# schematic_BAR.net
KiCad netlist of a schematic drawn in EAGLE
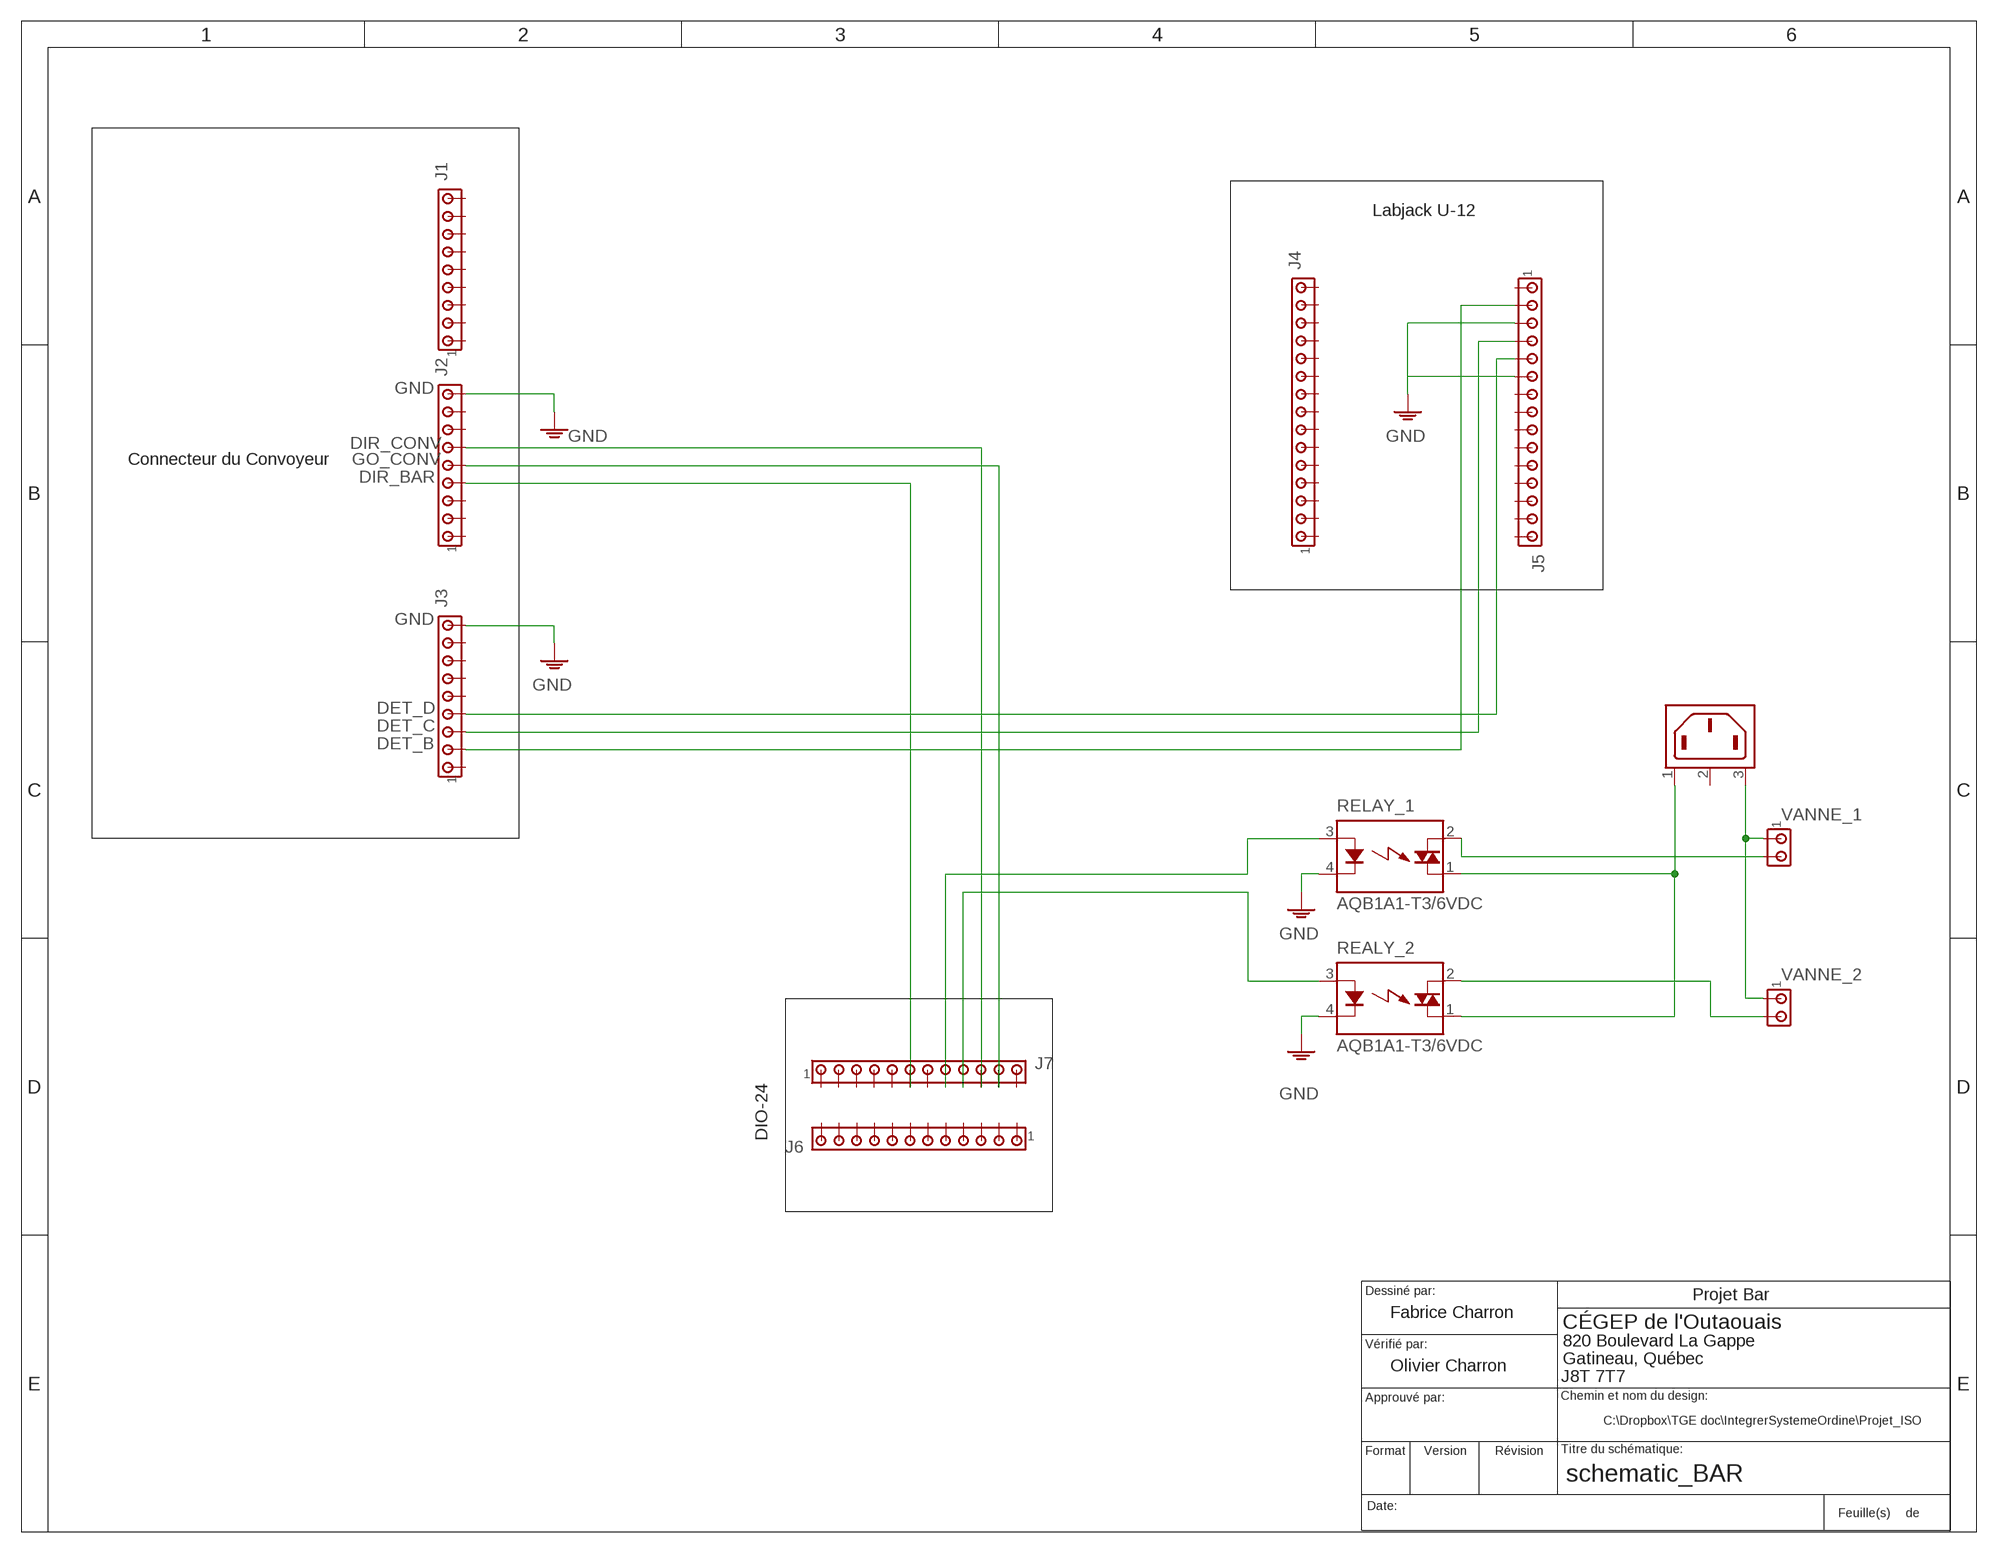
[diagram p0: schematic, sheet 1]

(export (version "E")
  (design (tool "Eeschema 10.0.6"))
  (components
    (comp (ref "J1")
      (value "MTA09-100")
      (footprint "eagle-import:10X09MTA")
      (libsource (lib "eagle-import") (part "MTA09-100"))
    )
    (comp (ref "J2")
      (value "MTA09-100")
      (footprint "eagle-import:10X09MTA")
      (libsource (lib "eagle-import") (part "MTA09-100"))
    )
    (comp (ref "J3")
      (value "MTA09-100")
      (footprint "eagle-import:10X09MTA")
      (libsource (lib "eagle-import") (part "MTA09-100"))
    )
    (comp (ref "J4")
      (value "MTA15-156")
      (footprint "eagle-import:1X15MTA")
      (libsource (lib "eagle-import") (part "MTA15-156"))
    )
    (comp (ref "J5")
      (value "MTA15-156")
      (footprint "eagle-import:1X15MTA")
      (libsource (lib "eagle-import") (part "MTA15-156"))
    )
    (comp (ref "J6")
      (value "MTA12-156")
      (footprint "eagle-import:1X12MTA")
      (libsource (lib "eagle-import") (part "MTA12-156"))
    )
    (comp (ref "J7")
      (value "MTA12-156")
      (footprint "eagle-import:1X12MTA")
      (libsource (lib "eagle-import") (part "MTA12-156"))
    )
    (comp (ref "REALY_2")
      (value "AQB1A1-T3/6VDC")
      (footprint "eagle-import:AQ-B")
      (libsource (lib "eagle-import") (part "AQB1A1-T3/6VDC"))
    )
    (comp (ref "RELAY_1")
      (value "AQB1A1-T3/6VDC")
      (footprint "eagle-import:AQ-B")
      (libsource (lib "eagle-import") (part "AQB1A1-T3/6VDC"))
    )
    (comp (ref "SOURCE_120V")
      (value "6ESRM-P")
      (footprint "eagle-import:6ESRM-P")
      (fields (field (name "MF") "TYCO ELECTRONICS"))
      (libsource (lib "eagle-import") (part "6ESRM-P"))
    )
    (comp (ref "VANNE_1")
      (value "MTA02-100")
      (footprint "eagle-import:10X02MTA")
      (libsource (lib "eagle-import") (part "MTA02-100"))
    )
    (comp (ref "VANNE_2")
      (value "MTA02-100")
      (footprint "eagle-import:10X02MTA")
      (libsource (lib "eagle-import") (part "MTA02-100"))
    )
  )
  (nets
    (net (code "1") (name "/DET_B") (class "Default")
      (node (ref "J3") (pin "2") (pinfunction "2_2") (pintype "passive"))
      (node (ref "J5") (pin "2") (pinfunction "2_2") (pintype "passive"))
    )
    (net (code "2") (name "/DET_C") (class "Default")
      (node (ref "J3") (pin "3") (pinfunction "3_3") (pintype "passive"))
      (node (ref "J5") (pin "4") (pinfunction "4_4") (pintype "passive"))
    )
    (net (code "3") (name "/DET_D") (class "Default")
      (node (ref "J3") (pin "4") (pinfunction "4_4") (pintype "passive"))
      (node (ref "J5") (pin "5") (pinfunction "5_5") (pintype "passive"))
    )
    (net (code "4") (name "/DIR_BAR") (class "Default")
      (node (ref "J2") (pin "4") (pinfunction "4_4") (pintype "passive"))
      (node (ref "J7") (pin "6") (pinfunction "6_6") (pintype "passive"))
    )
    (net (code "5") (name "/DIR_CONV") (class "Default")
      (node (ref "J2") (pin "6") (pinfunction "6_6") (pintype "passive"))
      (node (ref "J7") (pin "10") (pinfunction "10_10") (pintype "passive"))
    )
    (net (code "6") (name "/GO_CONV") (class "Default")
      (node (ref "J2") (pin "5") (pinfunction "5_5") (pintype "passive"))
      (node (ref "J7") (pin "11") (pinfunction "11_11") (pintype "passive"))
    )
    (net (code "7") (name "GND") (class "Default")
      (node (ref "J2") (pin "9") (pinfunction "9_9") (pintype "passive"))
      (node (ref "J3") (pin "9") (pinfunction "9_9") (pintype "passive"))
      (node (ref "J5") (pin "3") (pinfunction "3_3") (pintype "passive"))
      (node (ref "J5") (pin "6") (pinfunction "6_6") (pintype "passive"))
      (node (ref "REALY_2") (pin "4") (pinfunction "K_4") (pintype "passive"))
      (node (ref "RELAY_1") (pin "4") (pinfunction "K_4") (pintype "passive"))
    )
    (net (code "8") (name "Net-(REALY_2-A)") (class "Default")
      (node (ref "J7") (pin "9") (pinfunction "9_9") (pintype "passive"))
      (node (ref "REALY_2") (pin "3") (pinfunction "A_3") (pintype "passive"))
    )
    (net (code "9") (name "Net-(REALY_2-DS1)") (class "Default")
      (node (ref "REALY_2") (pin "2") (pinfunction "DS1_2") (pintype "passive"))
      (node (ref "VANNE_2") (pin "2") (pinfunction "2_2") (pintype "passive"))
    )
    (net (code "10") (name "Net-(REALY_2-DS2)") (class "Default")
      (node (ref "REALY_2") (pin "1") (pinfunction "DS2_1") (pintype "passive"))
      (node (ref "RELAY_1") (pin "1") (pinfunction "DS2_1") (pintype "passive"))
      (node (ref "SOURCE_120V") (pin "1") (pinfunction "AC1_1") (pintype "passive"))
    )
    (net (code "11") (name "Net-(RELAY_1-A)") (class "Default")
      (node (ref "J7") (pin "8") (pinfunction "8_8") (pintype "passive"))
      (node (ref "RELAY_1") (pin "3") (pinfunction "A_3") (pintype "passive"))
    )
    (net (code "12") (name "Net-(RELAY_1-DS1)") (class "Default")
      (node (ref "RELAY_1") (pin "2") (pinfunction "DS1_2") (pintype "passive"))
      (node (ref "VANNE_1") (pin "2") (pinfunction "2_2") (pintype "passive"))
    )
    (net (code "13") (name "Net-(SOURCE_120V-AC2)") (class "Default")
      (node (ref "SOURCE_120V") (pin "3") (pinfunction "AC2_3") (pintype "passive"))
      (node (ref "VANNE_1") (pin "1") (pinfunction "1_1") (pintype "passive"))
      (node (ref "VANNE_2") (pin "1") (pinfunction "1_1") (pintype "passive"))
    )
    (net (code "14") (name "unconnected-(J1-Pad1)") (class "Default")
      (node (ref "J1") (pin "1") (pinfunction "1_1") (pintype "passive"))
    )
    (net (code "15") (name "unconnected-(J1-Pad2)") (class "Default")
      (node (ref "J1") (pin "2") (pinfunction "2_2") (pintype "passive"))
    )
    (net (code "16") (name "unconnected-(J1-Pad3)") (class "Default")
      (node (ref "J1") (pin "3") (pinfunction "3_3") (pintype "passive"))
    )
    (net (code "17") (name "unconnected-(J1-Pad4)") (class "Default")
      (node (ref "J1") (pin "4") (pinfunction "4_4") (pintype "passive"))
    )
    (net (code "18") (name "unconnected-(J1-Pad5)") (class "Default")
      (node (ref "J1") (pin "5") (pinfunction "5_5") (pintype "passive"))
    )
    (net (code "19") (name "unconnected-(J1-Pad6)") (class "Default")
      (node (ref "J1") (pin "6") (pinfunction "6_6") (pintype "passive"))
    )
    (net (code "20") (name "unconnected-(J1-Pad7)") (class "Default")
      (node (ref "J1") (pin "7") (pinfunction "7_7") (pintype "passive"))
    )
    (net (code "21") (name "unconnected-(J1-Pad8)") (class "Default")
      (node (ref "J1") (pin "8") (pinfunction "8_8") (pintype "passive"))
    )
    (net (code "22") (name "unconnected-(J1-Pad9)") (class "Default")
      (node (ref "J1") (pin "9") (pinfunction "9_9") (pintype "passive"))
    )
    (net (code "23") (name "unconnected-(J2-Pad1)") (class "Default")
      (node (ref "J2") (pin "1") (pinfunction "1_1") (pintype "passive"))
    )
    (net (code "24") (name "unconnected-(J2-Pad2)") (class "Default")
      (node (ref "J2") (pin "2") (pinfunction "2_2") (pintype "passive"))
    )
    (net (code "25") (name "unconnected-(J2-Pad3)") (class "Default")
      (node (ref "J2") (pin "3") (pinfunction "3_3") (pintype "passive"))
    )
    (net (code "26") (name "unconnected-(J2-Pad7)") (class "Default")
      (node (ref "J2") (pin "7") (pinfunction "7_7") (pintype "passive"))
    )
    (net (code "27") (name "unconnected-(J2-Pad8)") (class "Default")
      (node (ref "J2") (pin "8") (pinfunction "8_8") (pintype "passive"))
    )
    (net (code "28") (name "unconnected-(J3-Pad1)") (class "Default")
      (node (ref "J3") (pin "1") (pinfunction "1_1") (pintype "passive"))
    )
    (net (code "29") (name "unconnected-(J3-Pad5)") (class "Default")
      (node (ref "J3") (pin "5") (pinfunction "5_5") (pintype "passive"))
    )
    (net (code "30") (name "unconnected-(J3-Pad6)") (class "Default")
      (node (ref "J3") (pin "6") (pinfunction "6_6") (pintype "passive"))
    )
    (net (code "31") (name "unconnected-(J3-Pad7)") (class "Default")
      (node (ref "J3") (pin "7") (pinfunction "7_7") (pintype "passive"))
    )
    (net (code "32") (name "unconnected-(J3-Pad8)") (class "Default")
      (node (ref "J3") (pin "8") (pinfunction "8_8") (pintype "passive"))
    )
    (net (code "33") (name "unconnected-(J4-Pad1)") (class "Default")
      (node (ref "J4") (pin "1") (pinfunction "1_1") (pintype "passive"))
    )
    (net (code "34") (name "unconnected-(J4-Pad2)") (class "Default")
      (node (ref "J4") (pin "2") (pinfunction "2_2") (pintype "passive"))
    )
    (net (code "35") (name "unconnected-(J4-Pad3)") (class "Default")
      (node (ref "J4") (pin "3") (pinfunction "3_3") (pintype "passive"))
    )
    (net (code "36") (name "unconnected-(J4-Pad4)") (class "Default")
      (node (ref "J4") (pin "4") (pinfunction "4_4") (pintype "passive"))
    )
    (net (code "37") (name "unconnected-(J4-Pad5)") (class "Default")
      (node (ref "J4") (pin "5") (pinfunction "5_5") (pintype "passive"))
    )
    (net (code "38") (name "unconnected-(J4-Pad6)") (class "Default")
      (node (ref "J4") (pin "6") (pinfunction "6_6") (pintype "passive"))
    )
    (net (code "39") (name "unconnected-(J4-Pad7)") (class "Default")
      (node (ref "J4") (pin "7") (pinfunction "7_7") (pintype "passive"))
    )
    (net (code "40") (name "unconnected-(J4-Pad8)") (class "Default")
      (node (ref "J4") (pin "8") (pinfunction "8_8") (pintype "passive"))
    )
    (net (code "41") (name "unconnected-(J4-Pad9)") (class "Default")
      (node (ref "J4") (pin "9") (pinfunction "9_9") (pintype "passive"))
    )
    (net (code "42") (name "unconnected-(J4-Pad10)") (class "Default")
      (node (ref "J4") (pin "10") (pinfunction "10_10") (pintype "passive"))
    )
    (net (code "43") (name "unconnected-(J4-Pad11)") (class "Default")
      (node (ref "J4") (pin "11") (pinfunction "11_11") (pintype "passive"))
    )
    (net (code "44") (name "unconnected-(J4-Pad12)") (class "Default")
      (node (ref "J4") (pin "12") (pinfunction "12_12") (pintype "passive"))
    )
    (net (code "45") (name "unconnected-(J4-Pad13)") (class "Default")
      (node (ref "J4") (pin "13") (pinfunction "13_13") (pintype "passive"))
    )
    (net (code "46") (name "unconnected-(J4-Pad14)") (class "Default")
      (node (ref "J4") (pin "14") (pinfunction "14_14") (pintype "passive"))
    )
    (net (code "47") (name "unconnected-(J4-Pad15)") (class "Default")
      (node (ref "J4") (pin "15") (pinfunction "15_15") (pintype "passive"))
    )
    (net (code "48") (name "unconnected-(J5-Pad1)") (class "Default")
      (node (ref "J5") (pin "1") (pinfunction "1_1") (pintype "passive"))
    )
    (net (code "49") (name "unconnected-(J5-Pad7)") (class "Default")
      (node (ref "J5") (pin "7") (pinfunction "7_7") (pintype "passive"))
    )
    (net (code "50") (name "unconnected-(J5-Pad8)") (class "Default")
      (node (ref "J5") (pin "8") (pinfunction "8_8") (pintype "passive"))
    )
    (net (code "51") (name "unconnected-(J5-Pad9)") (class "Default")
      (node (ref "J5") (pin "9") (pinfunction "9_9") (pintype "passive"))
    )
    (net (code "52") (name "unconnected-(J5-Pad10)") (class "Default")
      (node (ref "J5") (pin "10") (pinfunction "10_10") (pintype "passive"))
    )
    (net (code "53") (name "unconnected-(J5-Pad11)") (class "Default")
      (node (ref "J5") (pin "11") (pinfunction "11_11") (pintype "passive"))
    )
    (net (code "54") (name "unconnected-(J5-Pad12)") (class "Default")
      (node (ref "J5") (pin "12") (pinfunction "12_12") (pintype "passive"))
    )
    (net (code "55") (name "unconnected-(J5-Pad13)") (class "Default")
      (node (ref "J5") (pin "13") (pinfunction "13_13") (pintype "passive"))
    )
    (net (code "56") (name "unconnected-(J5-Pad14)") (class "Default")
      (node (ref "J5") (pin "14") (pinfunction "14_14") (pintype "passive"))
    )
    (net (code "57") (name "unconnected-(J5-Pad15)") (class "Default")
      (node (ref "J5") (pin "15") (pinfunction "15_15") (pintype "passive"))
    )
    (net (code "58") (name "unconnected-(J6-Pad1)") (class "Default")
      (node (ref "J6") (pin "1") (pinfunction "1_1") (pintype "passive"))
    )
    (net (code "59") (name "unconnected-(J6-Pad2)") (class "Default")
      (node (ref "J6") (pin "2") (pinfunction "2_2") (pintype "passive"))
    )
    (net (code "60") (name "unconnected-(J6-Pad3)") (class "Default")
      (node (ref "J6") (pin "3") (pinfunction "3_3") (pintype "passive"))
    )
    (net (code "61") (name "unconnected-(J6-Pad4)") (class "Default")
      (node (ref "J6") (pin "4") (pinfunction "4_4") (pintype "passive"))
    )
    (net (code "62") (name "unconnected-(J6-Pad5)") (class "Default")
      (node (ref "J6") (pin "5") (pinfunction "5_5") (pintype "passive"))
    )
    (net (code "63") (name "unconnected-(J6-Pad6)") (class "Default")
      (node (ref "J6") (pin "6") (pinfunction "6_6") (pintype "passive"))
    )
    (net (code "64") (name "unconnected-(J6-Pad7)") (class "Default")
      (node (ref "J6") (pin "7") (pinfunction "7_7") (pintype "passive"))
    )
    (net (code "65") (name "unconnected-(J6-Pad8)") (class "Default")
      (node (ref "J6") (pin "8") (pinfunction "8_8") (pintype "passive"))
    )
    (net (code "66") (name "unconnected-(J6-Pad9)") (class "Default")
      (node (ref "J6") (pin "9") (pinfunction "9_9") (pintype "passive"))
    )
    (net (code "67") (name "unconnected-(J6-Pad10)") (class "Default")
      (node (ref "J6") (pin "10") (pinfunction "10_10") (pintype "passive"))
    )
    (net (code "68") (name "unconnected-(J6-Pad11)") (class "Default")
      (node (ref "J6") (pin "11") (pinfunction "11_11") (pintype "passive"))
    )
    (net (code "69") (name "unconnected-(J6-Pad12)") (class "Default")
      (node (ref "J6") (pin "12") (pinfunction "12_12") (pintype "passive"))
    )
    (net (code "70") (name "unconnected-(J7-Pad1)") (class "Default")
      (node (ref "J7") (pin "1") (pinfunction "1_1") (pintype "passive"))
    )
    (net (code "71") (name "unconnected-(J7-Pad2)") (class "Default")
      (node (ref "J7") (pin "2") (pinfunction "2_2") (pintype "passive"))
    )
    (net (code "72") (name "unconnected-(J7-Pad3)") (class "Default")
      (node (ref "J7") (pin "3") (pinfunction "3_3") (pintype "passive"))
    )
    (net (code "73") (name "unconnected-(J7-Pad4)") (class "Default")
      (node (ref "J7") (pin "4") (pinfunction "4_4") (pintype "passive"))
    )
    (net (code "74") (name "unconnected-(J7-Pad5)") (class "Default")
      (node (ref "J7") (pin "5") (pinfunction "5_5") (pintype "passive"))
    )
    (net (code "75") (name "unconnected-(J7-Pad7)") (class "Default")
      (node (ref "J7") (pin "7") (pinfunction "7_7") (pintype "passive"))
    )
    (net (code "76") (name "unconnected-(J7-Pad12)") (class "Default")
      (node (ref "J7") (pin "12") (pinfunction "12_12") (pintype "passive"))
    )
    (net (code "77") (name "unconnected-(SOURCE_120V-SH-Pad2)") (class "Default")
      (node (ref "SOURCE_120V") (pin "2") (pinfunction "SH_2") (pintype "passive"))
    )
  )
)
